# FRAM-SOIC.net
KiCad netlist of a schematic drawn in EAGLE
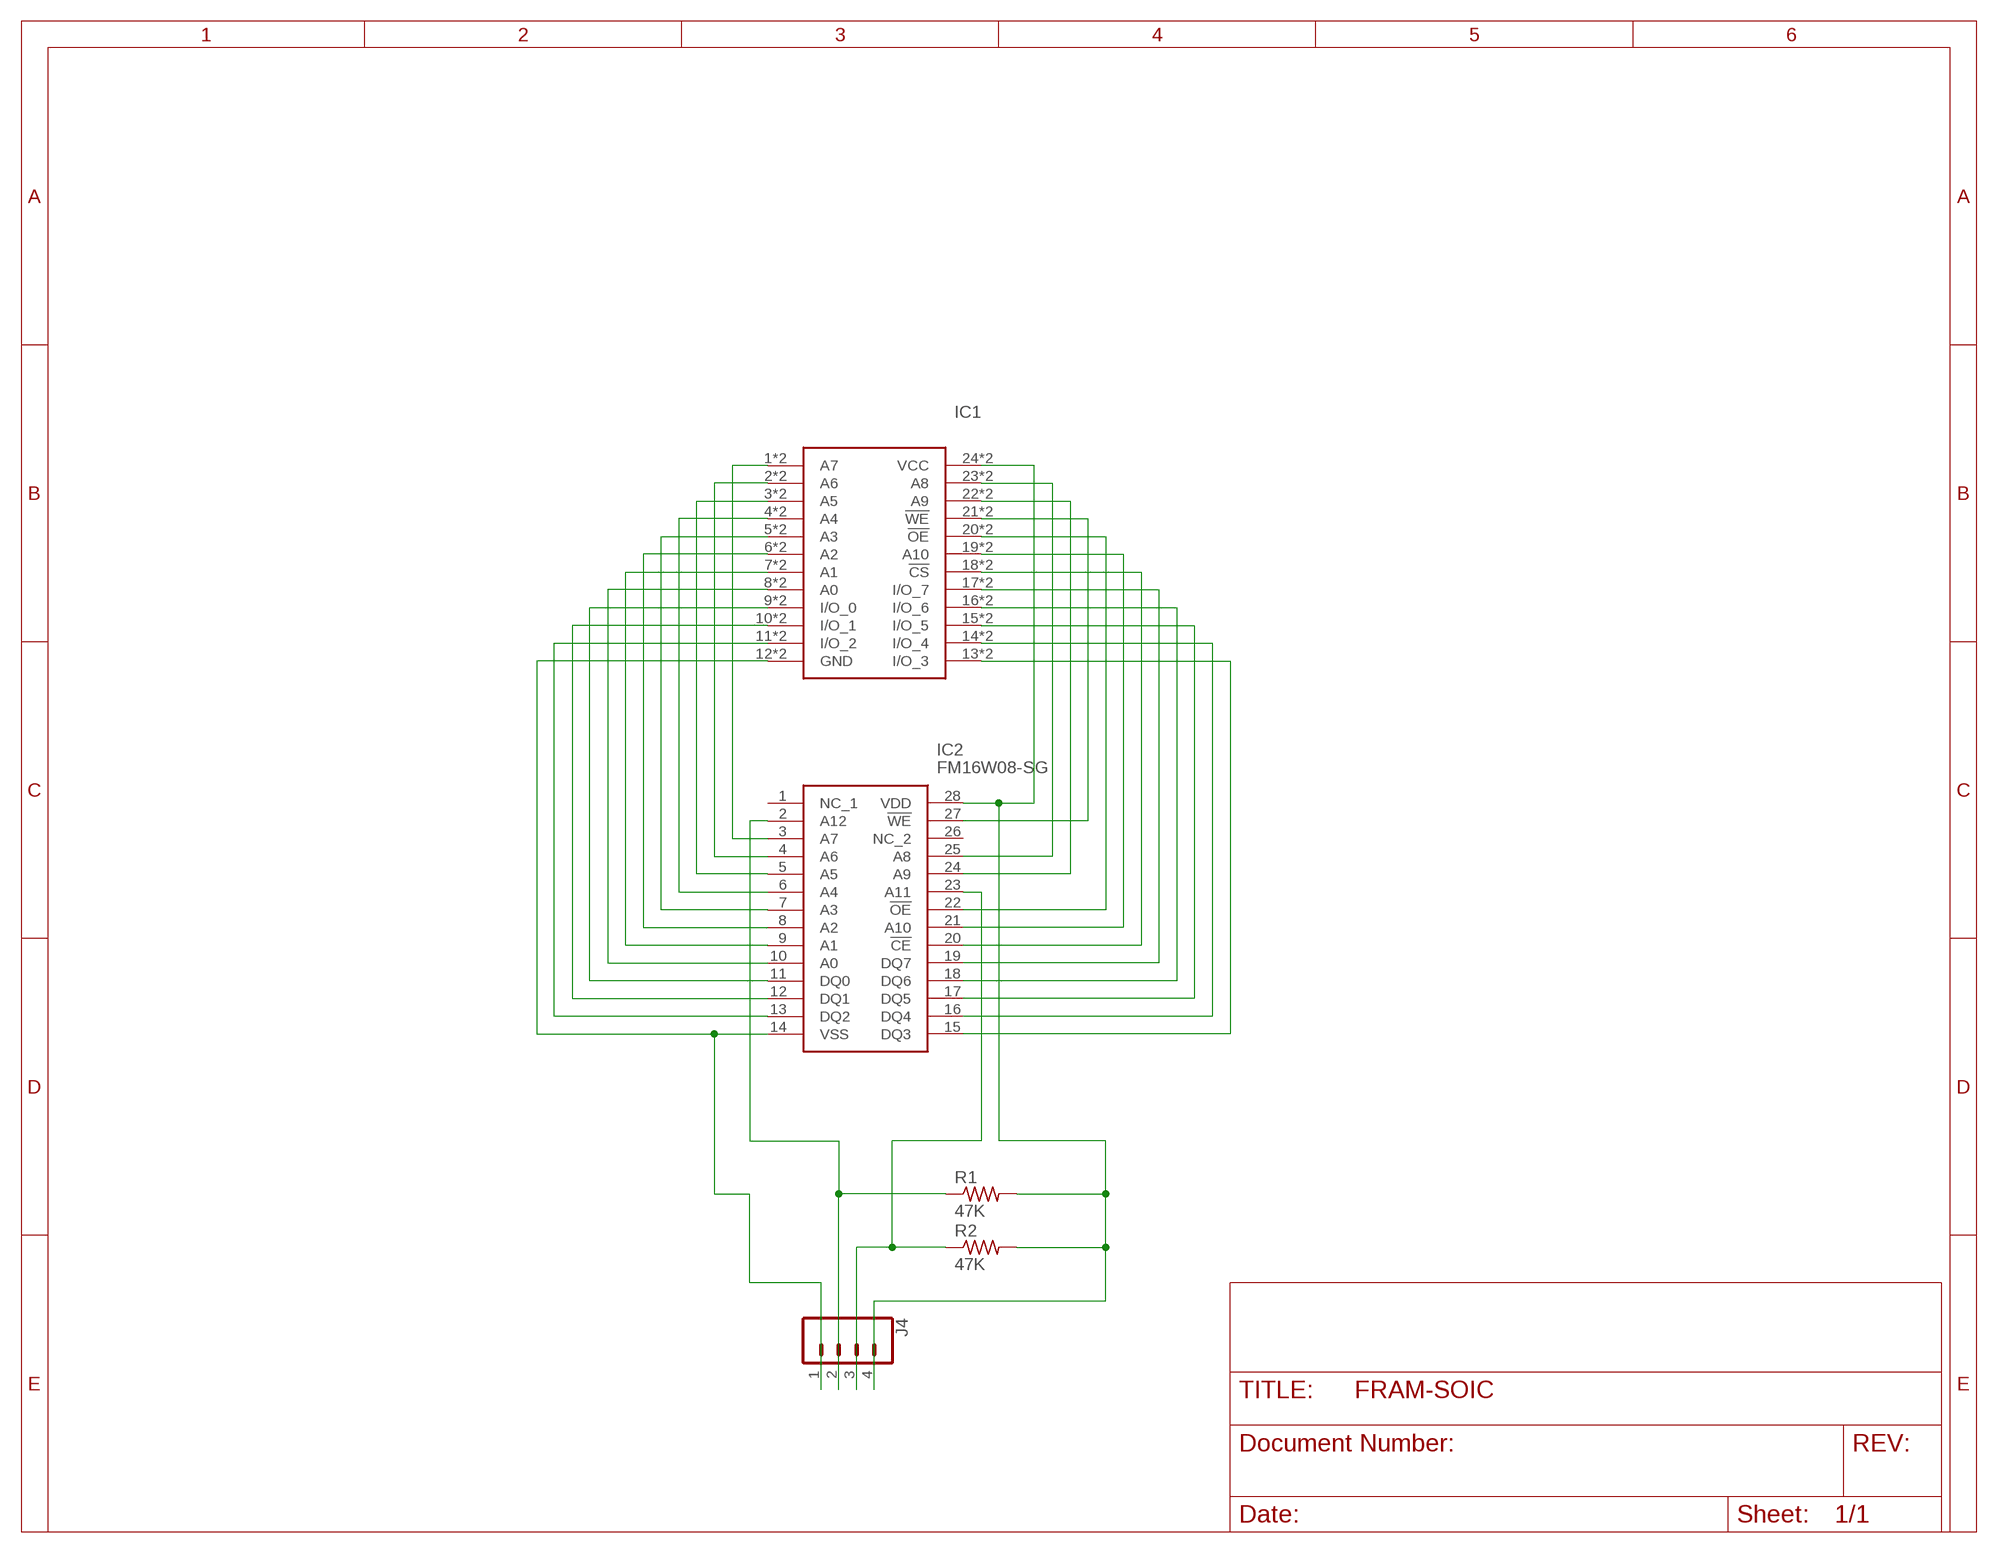
[diagram p0: schematic, sheet 1]

(export (version "E")
  (design (tool "Eeschema 10.0.6"))
  (components
    (comp (ref "IC1")
      (value "6116SOP-CASTELL")
      (footprint "eagle-import:CASTELL_SOIC-24N")
      (libsource (lib "eagle-import") (part "6116SOP-CASTELL"))
    )
    (comp (ref "IC2")
      (value "FM16W08-SG")
      (footprint "eagle-import:SOIC127P1032X267-28N")
      (fields (field (name "MOUSER_PART_NUMBER") "877-FM16W08-SG"))
      (libsource (lib "eagle-import") (part "FM16W08-SG"))
    )
    (comp (ref "J4")
      (value "CONN_04SMD_RA_FEMALE")
      (footprint "eagle-import:1X04_SMD_RA_FEMALE")
      (libsource (lib "eagle-import") (part "CONN_04SMD_RA_FEMALE"))
    )
    (comp (ref "R1")
      (value "47K")
      (footprint "eagle-import:R0603")
      (libsource (lib "eagle-import") (part "R-US_R0603"))
    )
    (comp (ref "R2")
      (value "47K")
      (footprint "eagle-import:R0603")
      (libsource (lib "eagle-import") (part "R-US_R0603"))
    )
  )
  (nets
    (net (code "1") (name "Net-(IC2-A0)") (class "Default")
      (node (ref "IC1") (pin "8") (pinfunction "A0_8") (pintype "bidirectional"))
      (node (ref "IC1") (pin "P$8") (pinfunction "A0_P$8") (pintype "bidirectional"))
      (node (ref "IC2") (pin "10") (pinfunction "A0_10") (pintype "input"))
    )
    (net (code "2") (name "Net-(IC2-A1)") (class "Default")
      (node (ref "IC1") (pin "7") (pinfunction "A1_7") (pintype "bidirectional"))
      (node (ref "IC1") (pin "P$7") (pinfunction "A1_P$7") (pintype "bidirectional"))
      (node (ref "IC2") (pin "9") (pinfunction "A1_9") (pintype "input"))
    )
    (net (code "3") (name "Net-(IC2-A2)") (class "Default")
      (node (ref "IC1") (pin "6") (pinfunction "A2_6") (pintype "bidirectional"))
      (node (ref "IC1") (pin "P$6") (pinfunction "A2_P$6") (pintype "bidirectional"))
      (node (ref "IC2") (pin "8") (pinfunction "A2_8") (pintype "input"))
    )
    (net (code "4") (name "Net-(IC2-A3)") (class "Default")
      (node (ref "IC1") (pin "5") (pinfunction "A3_5") (pintype "bidirectional"))
      (node (ref "IC1") (pin "P$5") (pinfunction "A3_P$5") (pintype "bidirectional"))
      (node (ref "IC2") (pin "7") (pinfunction "A3_7") (pintype "input"))
    )
    (net (code "5") (name "Net-(IC2-A4)") (class "Default")
      (node (ref "IC1") (pin "4") (pinfunction "A4_4") (pintype "bidirectional"))
      (node (ref "IC1") (pin "P$4") (pinfunction "A4_P$4") (pintype "bidirectional"))
      (node (ref "IC2") (pin "6") (pinfunction "A4_6") (pintype "input"))
    )
    (net (code "6") (name "Net-(IC2-A5)") (class "Default")
      (node (ref "IC1") (pin "3") (pinfunction "A5_3") (pintype "bidirectional"))
      (node (ref "IC1") (pin "P$3") (pinfunction "A5_P$3") (pintype "bidirectional"))
      (node (ref "IC2") (pin "5") (pinfunction "A5_5") (pintype "input"))
    )
    (net (code "7") (name "Net-(IC2-A6)") (class "Default")
      (node (ref "IC1") (pin "2") (pinfunction "A6_2") (pintype "bidirectional"))
      (node (ref "IC1") (pin "P$2") (pinfunction "A6_P$2") (pintype "bidirectional"))
      (node (ref "IC2") (pin "4") (pinfunction "A6_4") (pintype "input"))
    )
    (net (code "8") (name "Net-(IC2-A7)") (class "Default")
      (node (ref "IC1") (pin "1") (pinfunction "A7_1") (pintype "bidirectional"))
      (node (ref "IC1") (pin "P$1") (pinfunction "A7_P$1") (pintype "bidirectional"))
      (node (ref "IC2") (pin "3") (pinfunction "A7_3") (pintype "input"))
    )
    (net (code "9") (name "Net-(IC2-A8)") (class "Default")
      (node (ref "IC1") (pin "23") (pinfunction "A8_23") (pintype "bidirectional"))
      (node (ref "IC1") (pin "P$23") (pinfunction "A8_P$23") (pintype "bidirectional"))
      (node (ref "IC2") (pin "25") (pinfunction "A8_25") (pintype "input"))
    )
    (net (code "10") (name "Net-(IC2-A9)") (class "Default")
      (node (ref "IC1") (pin "22") (pinfunction "A9_22") (pintype "bidirectional"))
      (node (ref "IC1") (pin "P$22") (pinfunction "A9_P$22") (pintype "bidirectional"))
      (node (ref "IC2") (pin "24") (pinfunction "A9_24") (pintype "input"))
    )
    (net (code "11") (name "Net-(IC2-A10)") (class "Default")
      (node (ref "IC1") (pin "19") (pinfunction "A10_19") (pintype "bidirectional"))
      (node (ref "IC1") (pin "P$19") (pinfunction "A10_P$19") (pintype "bidirectional"))
      (node (ref "IC2") (pin "21") (pinfunction "A10_21") (pintype "input"))
    )
    (net (code "12") (name "Net-(IC2-A11)") (class "Default")
      (node (ref "IC2") (pin "23") (pinfunction "A11_23") (pintype "input"))
      (node (ref "J4") (pin "3") (pinfunction "3_3") (pintype "passive"))
      (node (ref "R2") (pin "1") (pinfunction "1_1") (pintype "passive"))
    )
    (net (code "13") (name "Net-(IC2-A12)") (class "Default")
      (node (ref "IC2") (pin "2") (pinfunction "A12_2") (pintype "input"))
      (node (ref "J4") (pin "2") (pinfunction "2_2") (pintype "passive"))
      (node (ref "R1") (pin "1") (pinfunction "1_1") (pintype "passive"))
    )
    (net (code "14") (name "Net-(IC2-DQ0)") (class "Default")
      (node (ref "IC1") (pin "9") (pinfunction "I/O_0_9") (pintype "bidirectional"))
      (node (ref "IC1") (pin "P$9") (pinfunction "I/O_0_P$9") (pintype "bidirectional"))
      (node (ref "IC2") (pin "11") (pinfunction "DQ0_11") (pintype "bidirectional"))
    )
    (net (code "15") (name "Net-(IC2-DQ1)") (class "Default")
      (node (ref "IC1") (pin "10") (pinfunction "I/O_1_10") (pintype "bidirectional"))
      (node (ref "IC1") (pin "P$10") (pinfunction "I/O_1_P$10") (pintype "bidirectional"))
      (node (ref "IC2") (pin "12") (pinfunction "DQ1_12") (pintype "bidirectional"))
    )
    (net (code "16") (name "Net-(IC2-DQ2)") (class "Default")
      (node (ref "IC1") (pin "11") (pinfunction "I/O_2_11") (pintype "bidirectional"))
      (node (ref "IC1") (pin "P$11") (pinfunction "I/O_2_P$11") (pintype "bidirectional"))
      (node (ref "IC2") (pin "13") (pinfunction "DQ2_13") (pintype "bidirectional"))
    )
    (net (code "17") (name "Net-(IC2-DQ3)") (class "Default")
      (node (ref "IC1") (pin "13") (pinfunction "I/O_3_13") (pintype "bidirectional"))
      (node (ref "IC1") (pin "P$13") (pinfunction "I/O_3_P$13") (pintype "bidirectional"))
      (node (ref "IC2") (pin "15") (pinfunction "DQ3_15") (pintype "bidirectional"))
    )
    (net (code "18") (name "Net-(IC2-DQ4)") (class "Default")
      (node (ref "IC1") (pin "14") (pinfunction "I/O_4_14") (pintype "bidirectional"))
      (node (ref "IC1") (pin "P$14") (pinfunction "I/O_4_P$14") (pintype "bidirectional"))
      (node (ref "IC2") (pin "16") (pinfunction "DQ4_16") (pintype "bidirectional"))
    )
    (net (code "19") (name "Net-(IC2-DQ5)") (class "Default")
      (node (ref "IC1") (pin "15") (pinfunction "I/O_5_15") (pintype "bidirectional"))
      (node (ref "IC1") (pin "P$15") (pinfunction "I/O_5_P$15") (pintype "bidirectional"))
      (node (ref "IC2") (pin "17") (pinfunction "DQ5_17") (pintype "bidirectional"))
    )
    (net (code "20") (name "Net-(IC2-DQ6)") (class "Default")
      (node (ref "IC1") (pin "16") (pinfunction "I/O_6_16") (pintype "bidirectional"))
      (node (ref "IC1") (pin "P$16") (pinfunction "I/O_6_P$16") (pintype "bidirectional"))
      (node (ref "IC2") (pin "18") (pinfunction "DQ6_18") (pintype "bidirectional"))
    )
    (net (code "21") (name "Net-(IC2-DQ7)") (class "Default")
      (node (ref "IC1") (pin "17") (pinfunction "I/O_7_17") (pintype "bidirectional"))
      (node (ref "IC1") (pin "P$17") (pinfunction "I/O_7_P$17") (pintype "bidirectional"))
      (node (ref "IC2") (pin "19") (pinfunction "DQ7_19") (pintype "bidirectional"))
    )
    (net (code "22") (name "Net-(IC2-VDD)") (class "Default")
      (node (ref "IC1") (pin "24") (pinfunction "VCC_24") (pintype "bidirectional"))
      (node (ref "IC1") (pin "P$24") (pinfunction "VCC_P$24") (pintype "bidirectional"))
      (node (ref "IC2") (pin "28") (pinfunction "VDD_28") (pintype "power_in"))
      (node (ref "J4") (pin "4") (pinfunction "4_4") (pintype "passive"))
      (node (ref "R1") (pin "2") (pinfunction "2_2") (pintype "passive"))
      (node (ref "R2") (pin "2") (pinfunction "2_2") (pintype "passive"))
    )
    (net (code "23") (name "Net-(IC2-VSS)") (class "Default")
      (node (ref "IC1") (pin "12") (pinfunction "GND_12") (pintype "bidirectional"))
      (node (ref "IC1") (pin "P$12") (pinfunction "GND_P$12") (pintype "bidirectional"))
      (node (ref "IC2") (pin "14") (pinfunction "VSS_14") (pintype "power_in"))
      (node (ref "J4") (pin "1") (pinfunction "1_1") (pintype "passive"))
    )
    (net (code "24") (name "Net-(IC2-~{CE})") (class "Default")
      (node (ref "IC1") (pin "18") (pinfunction "~{CS}_18") (pintype "bidirectional"))
      (node (ref "IC1") (pin "P$18") (pinfunction "~{CS}_P$18") (pintype "bidirectional"))
      (node (ref "IC2") (pin "20") (pinfunction "~{CE}_20") (pintype "input"))
    )
    (net (code "25") (name "Net-(IC2-~{OE})") (class "Default")
      (node (ref "IC1") (pin "20") (pinfunction "~{OE}_20") (pintype "bidirectional"))
      (node (ref "IC1") (pin "P$20") (pinfunction "~{OE}_P$20") (pintype "bidirectional"))
      (node (ref "IC2") (pin "22") (pinfunction "~{OE}_22") (pintype "input"))
    )
    (net (code "26") (name "Net-(IC2-~{WE})") (class "Default")
      (node (ref "IC1") (pin "21") (pinfunction "~{WE}_21") (pintype "bidirectional"))
      (node (ref "IC1") (pin "P$21") (pinfunction "~{WE}_P$21") (pintype "bidirectional"))
      (node (ref "IC2") (pin "27") (pinfunction "~{WE}_27") (pintype "input"))
    )
    (net (code "27") (name "unconnected-(IC2-NC_1-Pad1)") (class "Default")
      (node (ref "IC2") (pin "1") (pinfunction "NC_1_1") (pintype "bidirectional"))
    )
    (net (code "28") (name "unconnected-(IC2-NC_2-Pad26)") (class "Default")
      (node (ref "IC2") (pin "26") (pinfunction "NC_2_26") (pintype "bidirectional"))
    )
  )
)
